# breakoutResistor.net
KiCad netlist of a schematic drawn in EAGLE
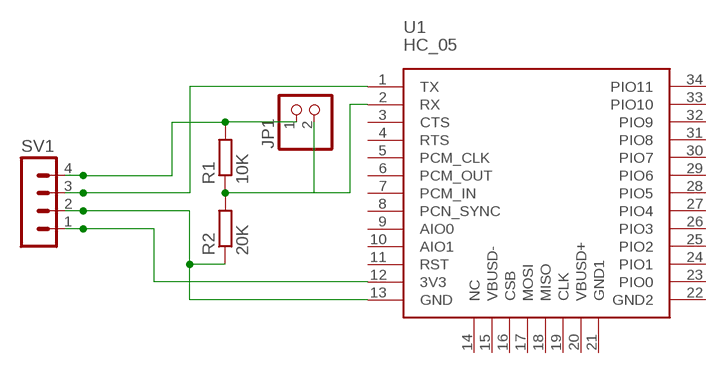
[diagram p0: schematic, sheet 1]

(export (version "E")
  (design (tool "Eeschema 10.0.6"))
  (components
    (comp (ref "JP1")
      (value "PINHD-1X2")
      (footprint "eagle-import:1X02")
      (libsource (lib "eagle-import") (part "PINHD-1X2"))
    )
    (comp (ref "R1")
      (value "10K")
      (footprint "eagle-import:R0805")
      (libsource (lib "eagle-import") (part "R-EU_R0805"))
    )
    (comp (ref "R2")
      (value "20K")
      (footprint "eagle-import:R0805")
      (libsource (lib "eagle-import") (part "R-EU_R0805"))
    )
    (comp (ref "SV1")
      (value "MA04-1")
      (footprint "eagle-import:MA04-1")
      (libsource (lib "eagle-import") (part "MA04-1"))
    )
    (comp (ref "U1")
      (value "HC_05")
      (footprint "eagle-import:BLUETOOTH_SMD")
      (libsource (lib "eagle-import") (part "HC_05"))
    )
  )
  (nets
    (net (code "1") (name "Net-(JP1-Pad1)") (class "Default")
      (node (ref "JP1") (pin "1") (pinfunction "1_1") (pintype "passive"))
      (node (ref "R1") (pin "2") (pinfunction "2_2") (pintype "passive"))
      (node (ref "SV1") (pin "4") (pinfunction "4_4") (pintype "passive"))
    )
    (net (code "2") (name "Net-(U1-3V3)") (class "Default")
      (node (ref "SV1") (pin "1") (pinfunction "1_1") (pintype "passive"))
      (node (ref "U1") (pin "12") (pinfunction "3V3_12") (pintype "bidirectional"))
    )
    (net (code "3") (name "Net-(U1-GND)") (class "Default")
      (node (ref "R2") (pin "1") (pinfunction "1_1") (pintype "passive"))
      (node (ref "SV1") (pin "2") (pinfunction "2_2") (pintype "passive"))
      (node (ref "U1") (pin "13") (pinfunction "GND_13") (pintype "bidirectional"))
    )
    (net (code "4") (name "Net-(U1-RX)") (class "Default")
      (node (ref "JP1") (pin "2") (pinfunction "2_2") (pintype "passive"))
      (node (ref "R1") (pin "1") (pinfunction "1_1") (pintype "passive"))
      (node (ref "R2") (pin "2") (pinfunction "2_2") (pintype "passive"))
      (node (ref "U1") (pin "2") (pinfunction "RX_2") (pintype "bidirectional"))
    )
    (net (code "5") (name "Net-(U1-TX)") (class "Default")
      (node (ref "SV1") (pin "3") (pinfunction "3_3") (pintype "passive"))
      (node (ref "U1") (pin "1") (pinfunction "TX_1") (pintype "bidirectional"))
    )
    (net (code "6") (name "unconnected-(U1-AIO0-Pad9)") (class "Default")
      (node (ref "U1") (pin "9") (pinfunction "AIO0_9") (pintype "bidirectional"))
    )
    (net (code "7") (name "unconnected-(U1-AIO1-Pad10)") (class "Default")
      (node (ref "U1") (pin "10") (pinfunction "AIO1_10") (pintype "bidirectional"))
    )
    (net (code "8") (name "unconnected-(U1-CLK-Pad19)") (class "Default")
      (node (ref "U1") (pin "19") (pinfunction "CLK_19") (pintype "bidirectional"))
    )
    (net (code "9") (name "unconnected-(U1-CSB-Pad16)") (class "Default")
      (node (ref "U1") (pin "16") (pinfunction "CSB_16") (pintype "bidirectional"))
    )
    (net (code "10") (name "unconnected-(U1-CTS-Pad3)") (class "Default")
      (node (ref "U1") (pin "3") (pinfunction "CTS_3") (pintype "bidirectional"))
    )
    (net (code "11") (name "unconnected-(U1-GND1-Pad21)") (class "Default")
      (node (ref "U1") (pin "21") (pinfunction "GND1_21") (pintype "bidirectional"))
    )
    (net (code "12") (name "unconnected-(U1-GND2-Pad22)") (class "Default")
      (node (ref "U1") (pin "22") (pinfunction "GND2_22") (pintype "bidirectional"))
    )
    (net (code "13") (name "unconnected-(U1-MISO-Pad18)") (class "Default")
      (node (ref "U1") (pin "18") (pinfunction "MISO_18") (pintype "bidirectional"))
    )
    (net (code "14") (name "unconnected-(U1-MOSI-Pad17)") (class "Default")
      (node (ref "U1") (pin "17") (pinfunction "MOSI_17") (pintype "bidirectional"))
    )
    (net (code "15") (name "unconnected-(U1-NC-Pad14)") (class "Default")
      (node (ref "U1") (pin "14") (pinfunction "NC_14") (pintype "bidirectional"))
    )
    (net (code "16") (name "unconnected-(U1-PCM_CLK-Pad5)") (class "Default")
      (node (ref "U1") (pin "5") (pinfunction "PCM_CLK_5") (pintype "bidirectional"))
    )
    (net (code "17") (name "unconnected-(U1-PCM_IN-Pad7)") (class "Default")
      (node (ref "U1") (pin "7") (pinfunction "PCM_IN_7") (pintype "bidirectional"))
    )
    (net (code "18") (name "unconnected-(U1-PCM_OUT-Pad6)") (class "Default")
      (node (ref "U1") (pin "6") (pinfunction "PCM_OUT_6") (pintype "bidirectional"))
    )
    (net (code "19") (name "unconnected-(U1-PCN_SYNC-Pad8)") (class "Default")
      (node (ref "U1") (pin "8") (pinfunction "PCN_SYNC_8") (pintype "bidirectional"))
    )
    (net (code "20") (name "unconnected-(U1-PIO0-Pad23)") (class "Default")
      (node (ref "U1") (pin "23") (pinfunction "PIO0_23") (pintype "bidirectional"))
    )
    (net (code "21") (name "unconnected-(U1-PIO1-Pad24)") (class "Default")
      (node (ref "U1") (pin "24") (pinfunction "PIO1_24") (pintype "bidirectional"))
    )
    (net (code "22") (name "unconnected-(U1-PIO2-Pad25)") (class "Default")
      (node (ref "U1") (pin "25") (pinfunction "PIO2_25") (pintype "bidirectional"))
    )
    (net (code "23") (name "unconnected-(U1-PIO3-Pad26)") (class "Default")
      (node (ref "U1") (pin "26") (pinfunction "PIO3_26") (pintype "bidirectional"))
    )
    (net (code "24") (name "unconnected-(U1-PIO4-Pad27)") (class "Default")
      (node (ref "U1") (pin "27") (pinfunction "PIO4_27") (pintype "bidirectional"))
    )
    (net (code "25") (name "unconnected-(U1-PIO5-Pad28)") (class "Default")
      (node (ref "U1") (pin "28") (pinfunction "PIO5_28") (pintype "bidirectional"))
    )
    (net (code "26") (name "unconnected-(U1-PIO6-Pad29)") (class "Default")
      (node (ref "U1") (pin "29") (pinfunction "PIO6_29") (pintype "bidirectional"))
    )
    (net (code "27") (name "unconnected-(U1-PIO7-Pad30)") (class "Default")
      (node (ref "U1") (pin "30") (pinfunction "PIO7_30") (pintype "bidirectional"))
    )
    (net (code "28") (name "unconnected-(U1-PIO8-Pad31)") (class "Default")
      (node (ref "U1") (pin "31") (pinfunction "PIO8_31") (pintype "bidirectional"))
    )
    (net (code "29") (name "unconnected-(U1-PIO9-Pad32)") (class "Default")
      (node (ref "U1") (pin "32") (pinfunction "PIO9_32") (pintype "bidirectional"))
    )
    (net (code "30") (name "unconnected-(U1-PIO10-Pad33)") (class "Default")
      (node (ref "U1") (pin "33") (pinfunction "PIO10_33") (pintype "bidirectional"))
    )
    (net (code "31") (name "unconnected-(U1-PIO11-Pad34)") (class "Default")
      (node (ref "U1") (pin "34") (pinfunction "PIO11_34") (pintype "bidirectional"))
    )
    (net (code "32") (name "unconnected-(U1-RST-Pad11)") (class "Default")
      (node (ref "U1") (pin "11") (pinfunction "RST_11") (pintype "bidirectional"))
    )
    (net (code "33") (name "unconnected-(U1-RTS-Pad4)") (class "Default")
      (node (ref "U1") (pin "4") (pinfunction "RTS_4") (pintype "bidirectional"))
    )
    (net (code "34") (name "unconnected-(U1-VBUSD+-Pad20)") (class "Default")
      (node (ref "U1") (pin "20") (pinfunction "VBUSD+_20") (pintype "bidirectional"))
    )
    (net (code "35") (name "unconnected-(U1-VBUSD--Pad15)") (class "Default")
      (node (ref "U1") (pin "15") (pinfunction "VBUSD-_15") (pintype "bidirectional"))
    )
  )
)
